# LPCB230_-_TC_INTERFACE.net
KiCad netlist of a schematic drawn in Altium Designer
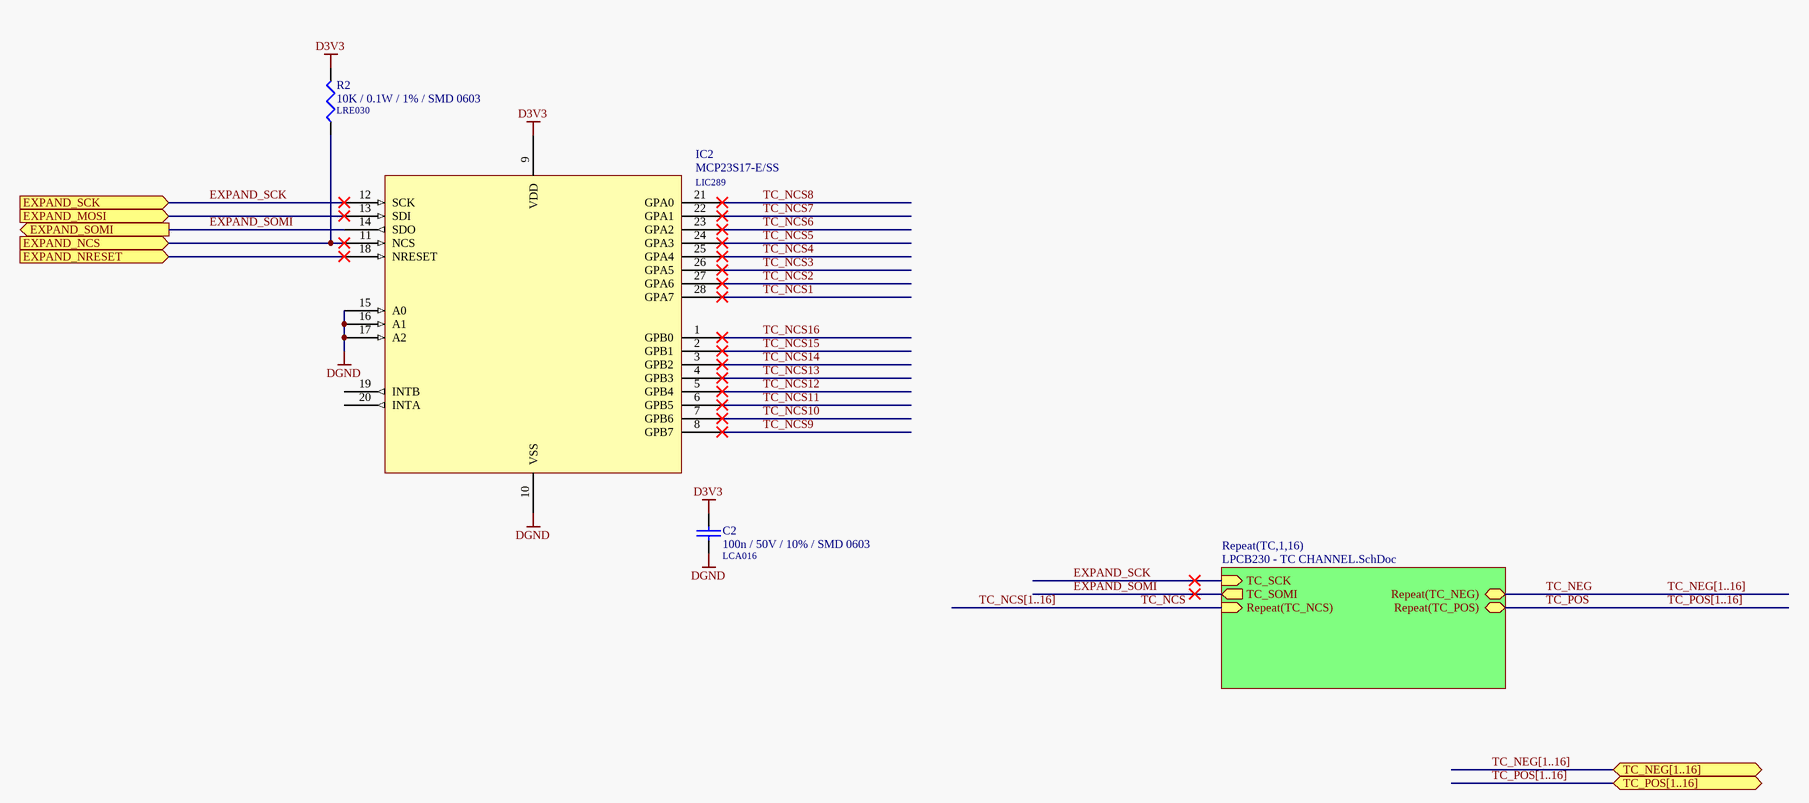
[diagram p0: LPCB230 - TC INTERFACE.SchDoc]

(export (version "E")
  (design (tool "Eeschema 10.0.6"))
  (components
    (comp (ref "C2")
      (value "100n / 50V / 10% / SMD 0603")
      (footprint "LFP011__CC1608-0603-IPC7351_B")
      (description "Capacitor, Ceramic Chip, 100nF (0.1uF), 50V, 5%, SMD 0603 [LCA016]")
      (fields (field (name "LDL_NUMBER") "LCA016"))
      (libsource (lib "LDL_Capacitors") (part "100n / 50V / 10% / SMD 0603"))
    )
    (comp (ref "IC2")
      (value "MCP23S17-E/SS")
      (footprint "LFP050__SSOP28")
      (description "IC, SPI IO Expander, 16bit, SMD SSOP28 [LIC289]")
      (fields (field (name "LDL_NUMBER") "LIC289"))
      (libsource (lib "LDL_Semiconductors") (part "MCP23S17-E/SS"))
    )
    (comp (ref "R2")
      (value "10K / 0.1W / 1% / SMD 0603")
      (footprint "LFP020__CR1608-0603-IPC7351_B")
      (description "Resistor, Ceramic Chip, 10K, 0.1W, 1%, SMD 0603 [LRE030]")
      (fields (field (name "LDL_NUMBER") "LRE030"))
      (libsource (lib "LDL_Resistors") (part "10K / 0.1W / 1% / SMD 0603"))
    )
  )
  (nets
    (net (code "33") (name "/EXPAND_MOSI") (class "Default")
      (node (ref "IC2") (pin "13") (pinfunction "SDI_13") (pintype "input+no_connect"))
    )
    (net (code "34") (name "/EXPAND_NCS") (class "Default")
      (node (ref "IC2") (pin "11") (pinfunction "NCS_11") (pintype "input"))
      (node (ref "R2") (pin "1") (pintype "passive"))
    )
    (net (code "35") (name "/EXPAND_NRESET") (class "Default")
      (node (ref "IC2") (pin "18") (pinfunction "NRESET_18") (pintype "input+no_connect"))
    )
    (net (code "36") (name "/EXPAND_SCK") (class "Default")
      (node (ref "IC2") (pin "12") (pinfunction "SCK_12") (pintype "input+no_connect"))
    )
    (net (code "37") (name "/EXPAND_SOMI") (class "Default")
      (node (ref "IC2") (pin "14") (pinfunction "SDO_14") (pintype "output"))
    )
    (net (code "39") (name "/TC_NCS1") (class "Default")
      (node (ref "IC2") (pin "28") (pinfunction "GPA7_28") (pintype "passive+no_connect"))
    )
    (net (code "40") (name "/TC_NCS2") (class "Default")
      (node (ref "IC2") (pin "27") (pinfunction "GPA6_27") (pintype "passive+no_connect"))
    )
    (net (code "41") (name "/TC_NCS3") (class "Default")
      (node (ref "IC2") (pin "26") (pinfunction "GPA5_26") (pintype "passive+no_connect"))
    )
    (net (code "42") (name "/TC_NCS4") (class "Default")
      (node (ref "IC2") (pin "25") (pinfunction "GPA4_25") (pintype "passive+no_connect"))
    )
    (net (code "43") (name "/TC_NCS5") (class "Default")
      (node (ref "IC2") (pin "24") (pinfunction "GPA3_24") (pintype "passive+no_connect"))
    )
    (net (code "44") (name "/TC_NCS6") (class "Default")
      (node (ref "IC2") (pin "23") (pinfunction "GPA2_23") (pintype "passive+no_connect"))
    )
    (net (code "45") (name "/TC_NCS7") (class "Default")
      (node (ref "IC2") (pin "22") (pinfunction "GPA1_22") (pintype "passive+no_connect"))
    )
    (net (code "46") (name "/TC_NCS8") (class "Default")
      (node (ref "IC2") (pin "21") (pinfunction "GPA0_21") (pintype "passive+no_connect"))
    )
    (net (code "47") (name "/TC_NCS9") (class "Default")
      (node (ref "IC2") (pin "8") (pinfunction "GPB7_8") (pintype "passive+no_connect"))
    )
    (net (code "48") (name "/TC_NCS10") (class "Default")
      (node (ref "IC2") (pin "7") (pinfunction "GPB6_7") (pintype "passive+no_connect"))
    )
    (net (code "49") (name "/TC_NCS11") (class "Default")
      (node (ref "IC2") (pin "6") (pinfunction "GPB5_6") (pintype "passive+no_connect"))
    )
    (net (code "50") (name "/TC_NCS12") (class "Default")
      (node (ref "IC2") (pin "5") (pinfunction "GPB4_5") (pintype "passive+no_connect"))
    )
    (net (code "51") (name "/TC_NCS13") (class "Default")
      (node (ref "IC2") (pin "4") (pinfunction "GPB3_4") (pintype "passive+no_connect"))
    )
    (net (code "52") (name "/TC_NCS14") (class "Default")
      (node (ref "IC2") (pin "3") (pinfunction "GPB2_3") (pintype "passive+no_connect"))
    )
    (net (code "53") (name "/TC_NCS15") (class "Default")
      (node (ref "IC2") (pin "2") (pinfunction "GPB1_2") (pintype "passive+no_connect"))
    )
    (net (code "54") (name "/TC_NCS16") (class "Default")
      (node (ref "IC2") (pin "1") (pinfunction "GPB0_1") (pintype "passive+no_connect"))
    )
    (net (code "60") (name "D3V3") (class "Default")
      (node (ref "C2") (pin "1") (pintype "passive"))
      (node (ref "IC2") (pin "9") (pinfunction "VDD_9") (pintype "power_in"))
      (node (ref "R2") (pin "2") (pintype "passive"))
    )
    (net (code "61") (name "DGND") (class "Default")
      (node (ref "C2") (pin "2") (pintype "passive"))
      (node (ref "IC2") (pin "10") (pinfunction "VSS_10") (pintype "power_in"))
      (node (ref "IC2") (pin "15") (pinfunction "A0_15") (pintype "input"))
      (node (ref "IC2") (pin "16") (pinfunction "A1_16") (pintype "input"))
      (node (ref "IC2") (pin "17") (pinfunction "A2_17") (pintype "input"))
    )
    (net (code "62") (name "unconnected-(IC2-INTA-Pad20)") (class "Default")
      (node (ref "IC2") (pin "20") (pinfunction "INTA_20") (pintype "output"))
    )
    (net (code "63") (name "unconnected-(IC2-INTB-Pad19)") (class "Default")
      (node (ref "IC2") (pin "19") (pinfunction "INTB_19") (pintype "output"))
    )
  )
)
